# Power.net
KiCad netlist of a schematic drawn in Altium Designer
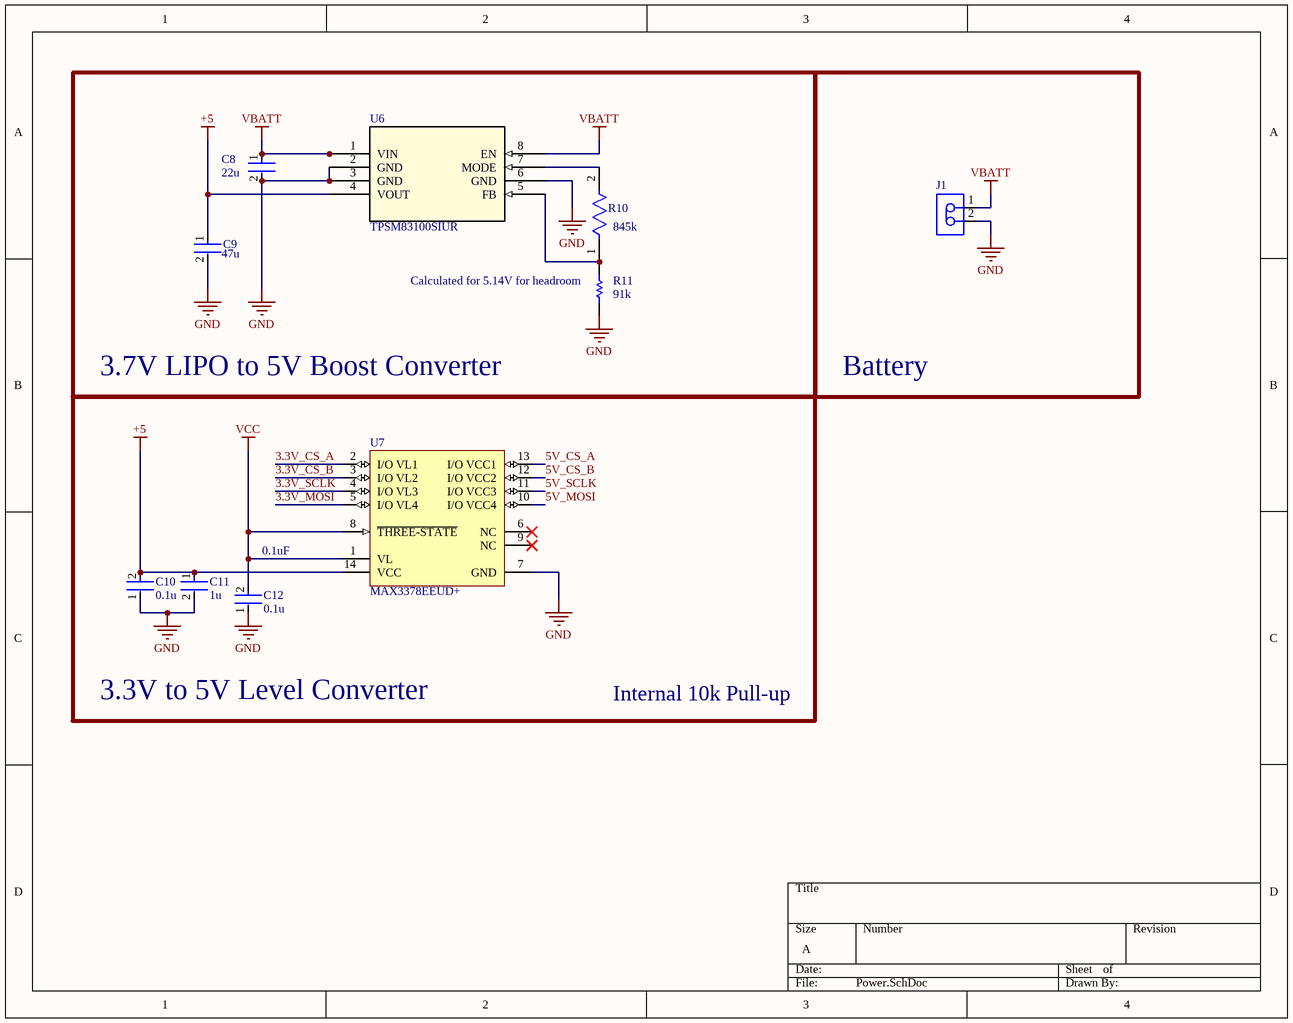
[diagram p0: Power.SchDoc]

(export (version "E")
  (design (tool "Eeschema 10.0.6"))
  (components
    (comp (ref "C8")
      (value "22u")
      (footprint "FP-GRM187-0_2-IPC_C")
      (description "Chip Multilayer Ceramic Capacitors for General Purpose, 0603, 22uF, X5R, 15%, 20%, 10V")
      (fields (field (name "TOLERANCE") "20%"))
      (libsource (lib "Altium Content Vault") (part "02cd4be3c70576c341d710602a673aa"))
    )
    (comp (ref "C9")
      (value "47u")
      (footprint "FP-GRM219-0_2-0_1-IPC_A")
      (description "Chip Multilayer Ceramic Capacitors for General Purpose, 0805, 47uF, X5R, 15%, 20%, 6.3V")
      (fields (field (name "TOLERANCE") "20%"))
      (libsource (lib "Altium Content Vault") (part "02cd4be3c70576c341d710602a673aa"))
    )
    (comp (ref "C10")
      (value "0.1u")
      (footprint "FP-GCJ188-0_2-IPC_C")
      (description "Cap Ceramic 0.1uF 50V X7R 10% Pad SMD 0603 Soft Termination +125°C Automotive T/R")
      (fields (field (name "TOLERANCE") "10%"))
      (libsource (lib "Altium Content Vault") (part "f23184f103b6ebe33a8c269c53dcba6"))
    )
    (comp (ref "C11")
      (value "1u")
      (footprint "FP-GCM188-0_1-IPC_B")
      (description "Ceramic Capacitor for Automotive 1uF  ±10% 16VDC X7R 0603 Paper T/R")
      (fields (field (name "VOLTAGE") "16V") (field (name "TOLERANCE") "10%"))
      (libsource (lib "Altium Content Vault") (part "02cd4be3c70576c341d710602a673aa"))
    )
    (comp (ref "C12")
      (value "0.1u")
      (footprint "FP-GCJ188-0_2-IPC_C")
      (description "Cap Ceramic 0.1uF 50V X7R 10% Pad SMD 0603 Soft Termination +125°C Automotive T/R")
      (fields (field (name "TOLERANCE") "10%"))
      (libsource (lib "Altium Content Vault") (part "f23184f103b6ebe33a8c269c53dcba6"))
    )
    (comp (ref "J1")
      (value "B2B-PH-K-S(LF)(SN)")
      (footprint "JST-B2B-PH-K-S_V")
      (fields (field (name "MANUFACTURER") "JST"))
      (libsource (lib "Altium Content Vault") (part "CN-2P-F-QF2"))
    )
    (comp (ref "R10")
      (value "845k")
      (footprint "FP-CR0603-IPC_B")
      (description "Thick Film Chip Resistors 0603 845kΩ 0.1W 1% 100ppm/°C")
      (fields (field (name "TOLERANCE") "1%"))
      (libsource (lib "Altium Content Vault") (part "1029c3af85768c4190bb7ad29bc67b5"))
    )
    (comp (ref "R11")
      (value "91k")
      (footprint "RESC1609X50X30NL10T20")
      (fields (field (name "PART NUMBER") "CRCW060391K0FKEA") (field (name "MANUFACTURER") "Vishay Dale"))
      (libsource (lib "Altium Content Vault") (part "RES"))
    )
    (comp (ref "U6")
      (value "TPSM83100SIUR")
      (footprint "MICROSIP8_SIU_TEX")
      (description "1.5-A high efficiency buck-boost module with integrated inductor")
      (libsource (lib "TPSM83100SIUR") (part "TPSM83100SIUR"))
    )
    (comp (ref "U7")
      (value "MAX3378EEUD+")
      (footprint "MAXM-U14+1_V")
      (libsource (lib "Altium Content Vault") (part "MAXM-MAX3378E-U14"))
    )
  )
  (nets
    (net (code "1") (name "+5") (class "Default")
      (node (ref "C10") (pin "2") (pinfunction "2_2") (pintype "passive"))
      (node (ref "C11") (pin "1") (pinfunction "1_1") (pintype "passive"))
      (node (ref "C9") (pin "1") (pinfunction "1_1") (pintype "passive"))
      (node (ref "U6") (pin "4") (pinfunction "VOUT_4") (pintype "power_in"))
      (node (ref "U7") (pin "14") (pinfunction "VCC_14") (pintype "power_in"))
    )
    (net (code "2") (name "/3.3V_CS_A") (class "Default")
      (node (ref "U7") (pin "2") (pinfunction "I/O_VL1_2") (pintype "bidirectional"))
    )
    (net (code "3") (name "/3.3V_CS_B") (class "Default")
      (node (ref "U7") (pin "3") (pinfunction "I/O_VL2_3") (pintype "bidirectional"))
    )
    (net (code "4") (name "/3.3V_MOSI") (class "Default")
      (node (ref "U7") (pin "5") (pinfunction "I/O_VL4_5") (pintype "bidirectional"))
    )
    (net (code "5") (name "/3.3V_SCLK") (class "Default")
      (node (ref "U7") (pin "4") (pinfunction "I/O_VL3_4") (pintype "bidirectional"))
    )
    (net (code "6") (name "/5V_CS_A") (class "Default")
      (node (ref "U7") (pin "13") (pinfunction "I/O_VCC1_13") (pintype "bidirectional"))
    )
    (net (code "7") (name "/5V_CS_B") (class "Default")
      (node (ref "U7") (pin "12") (pinfunction "I/O_VCC2_12") (pintype "bidirectional"))
    )
    (net (code "8") (name "/5V_MOSI") (class "Default")
      (node (ref "U7") (pin "10") (pinfunction "I/O_VCC4_10") (pintype "bidirectional"))
    )
    (net (code "9") (name "/5V_SCLK") (class "Default")
      (node (ref "U7") (pin "11") (pinfunction "I/O_VCC3_11") (pintype "bidirectional"))
    )
    (net (code "10") (name "GND") (class "Default")
      (node (ref "C10") (pin "1") (pinfunction "1_1") (pintype "passive"))
      (node (ref "C11") (pin "2") (pinfunction "2_2") (pintype "passive"))
      (node (ref "C12") (pin "1") (pinfunction "1_1") (pintype "passive"))
      (node (ref "C8") (pin "2") (pinfunction "2_2") (pintype "passive"))
      (node (ref "C9") (pin "2") (pinfunction "2_2") (pintype "passive"))
      (node (ref "J1") (pin "2") (pinfunction "2_2") (pintype "passive"))
      (node (ref "R11") (pin "1") (pinfunction "1_1") (pintype "passive"))
      (node (ref "U6") (pin "2") (pinfunction "GND_2") (pintype "power_in"))
      (node (ref "U6") (pin "3") (pinfunction "GND_3") (pintype "power_in"))
      (node (ref "U6") (pin "6") (pinfunction "GND_6") (pintype "power_in"))
      (node (ref "U7") (pin "7") (pinfunction "GND_7") (pintype "power_in"))
    )
    (net (code "11") (name "Net-(U6-FB)") (class "Default")
      (node (ref "R10") (pin "1") (pinfunction "1_1") (pintype "passive"))
      (node (ref "R11") (pin "2") (pinfunction "2_2") (pintype "passive"))
      (node (ref "U6") (pin "5") (pinfunction "FB_5") (pintype "input"))
    )
    (net (code "12") (name "Net-(U6-MODE)") (class "Default")
      (node (ref "R10") (pin "2") (pinfunction "2_2") (pintype "passive"))
      (node (ref "U6") (pin "7") (pinfunction "MODE_7") (pintype "input"))
    )
    (net (code "13") (name "VBATT") (class "Default")
      (node (ref "C8") (pin "1") (pinfunction "1_1") (pintype "passive"))
      (node (ref "J1") (pin "1") (pinfunction "1_1") (pintype "passive"))
      (node (ref "U6") (pin "1") (pinfunction "VIN_1") (pintype "power_in"))
      (node (ref "U6") (pin "8") (pinfunction "EN_8") (pintype "input"))
    )
    (net (code "14") (name "VCC") (class "Default")
      (node (ref "C12") (pin "2") (pinfunction "2_2") (pintype "passive"))
      (node (ref "U7") (pin "1") (pinfunction "VL_1") (pintype "power_in"))
      (node (ref "U7") (pin "8") (pinfunction "~{THREE-STATE}_8") (pintype "input"))
    )
    (net (code "15") (name "unconnected-(U7-NC-Pad6)") (class "Default")
      (node (ref "U7") (pin "6") (pinfunction "NC_6") (pintype "passive+no_connect"))
    )
    (net (code "16") (name "unconnected-(U7-NC-Pad9)") (class "Default")
      (node (ref "U7") (pin "9") (pinfunction "NC_9") (pintype "passive+no_connect"))
    )
  )
)
